# SCH_PCB_Project.net
KiCad netlist of a schematic drawn in EasyEDA
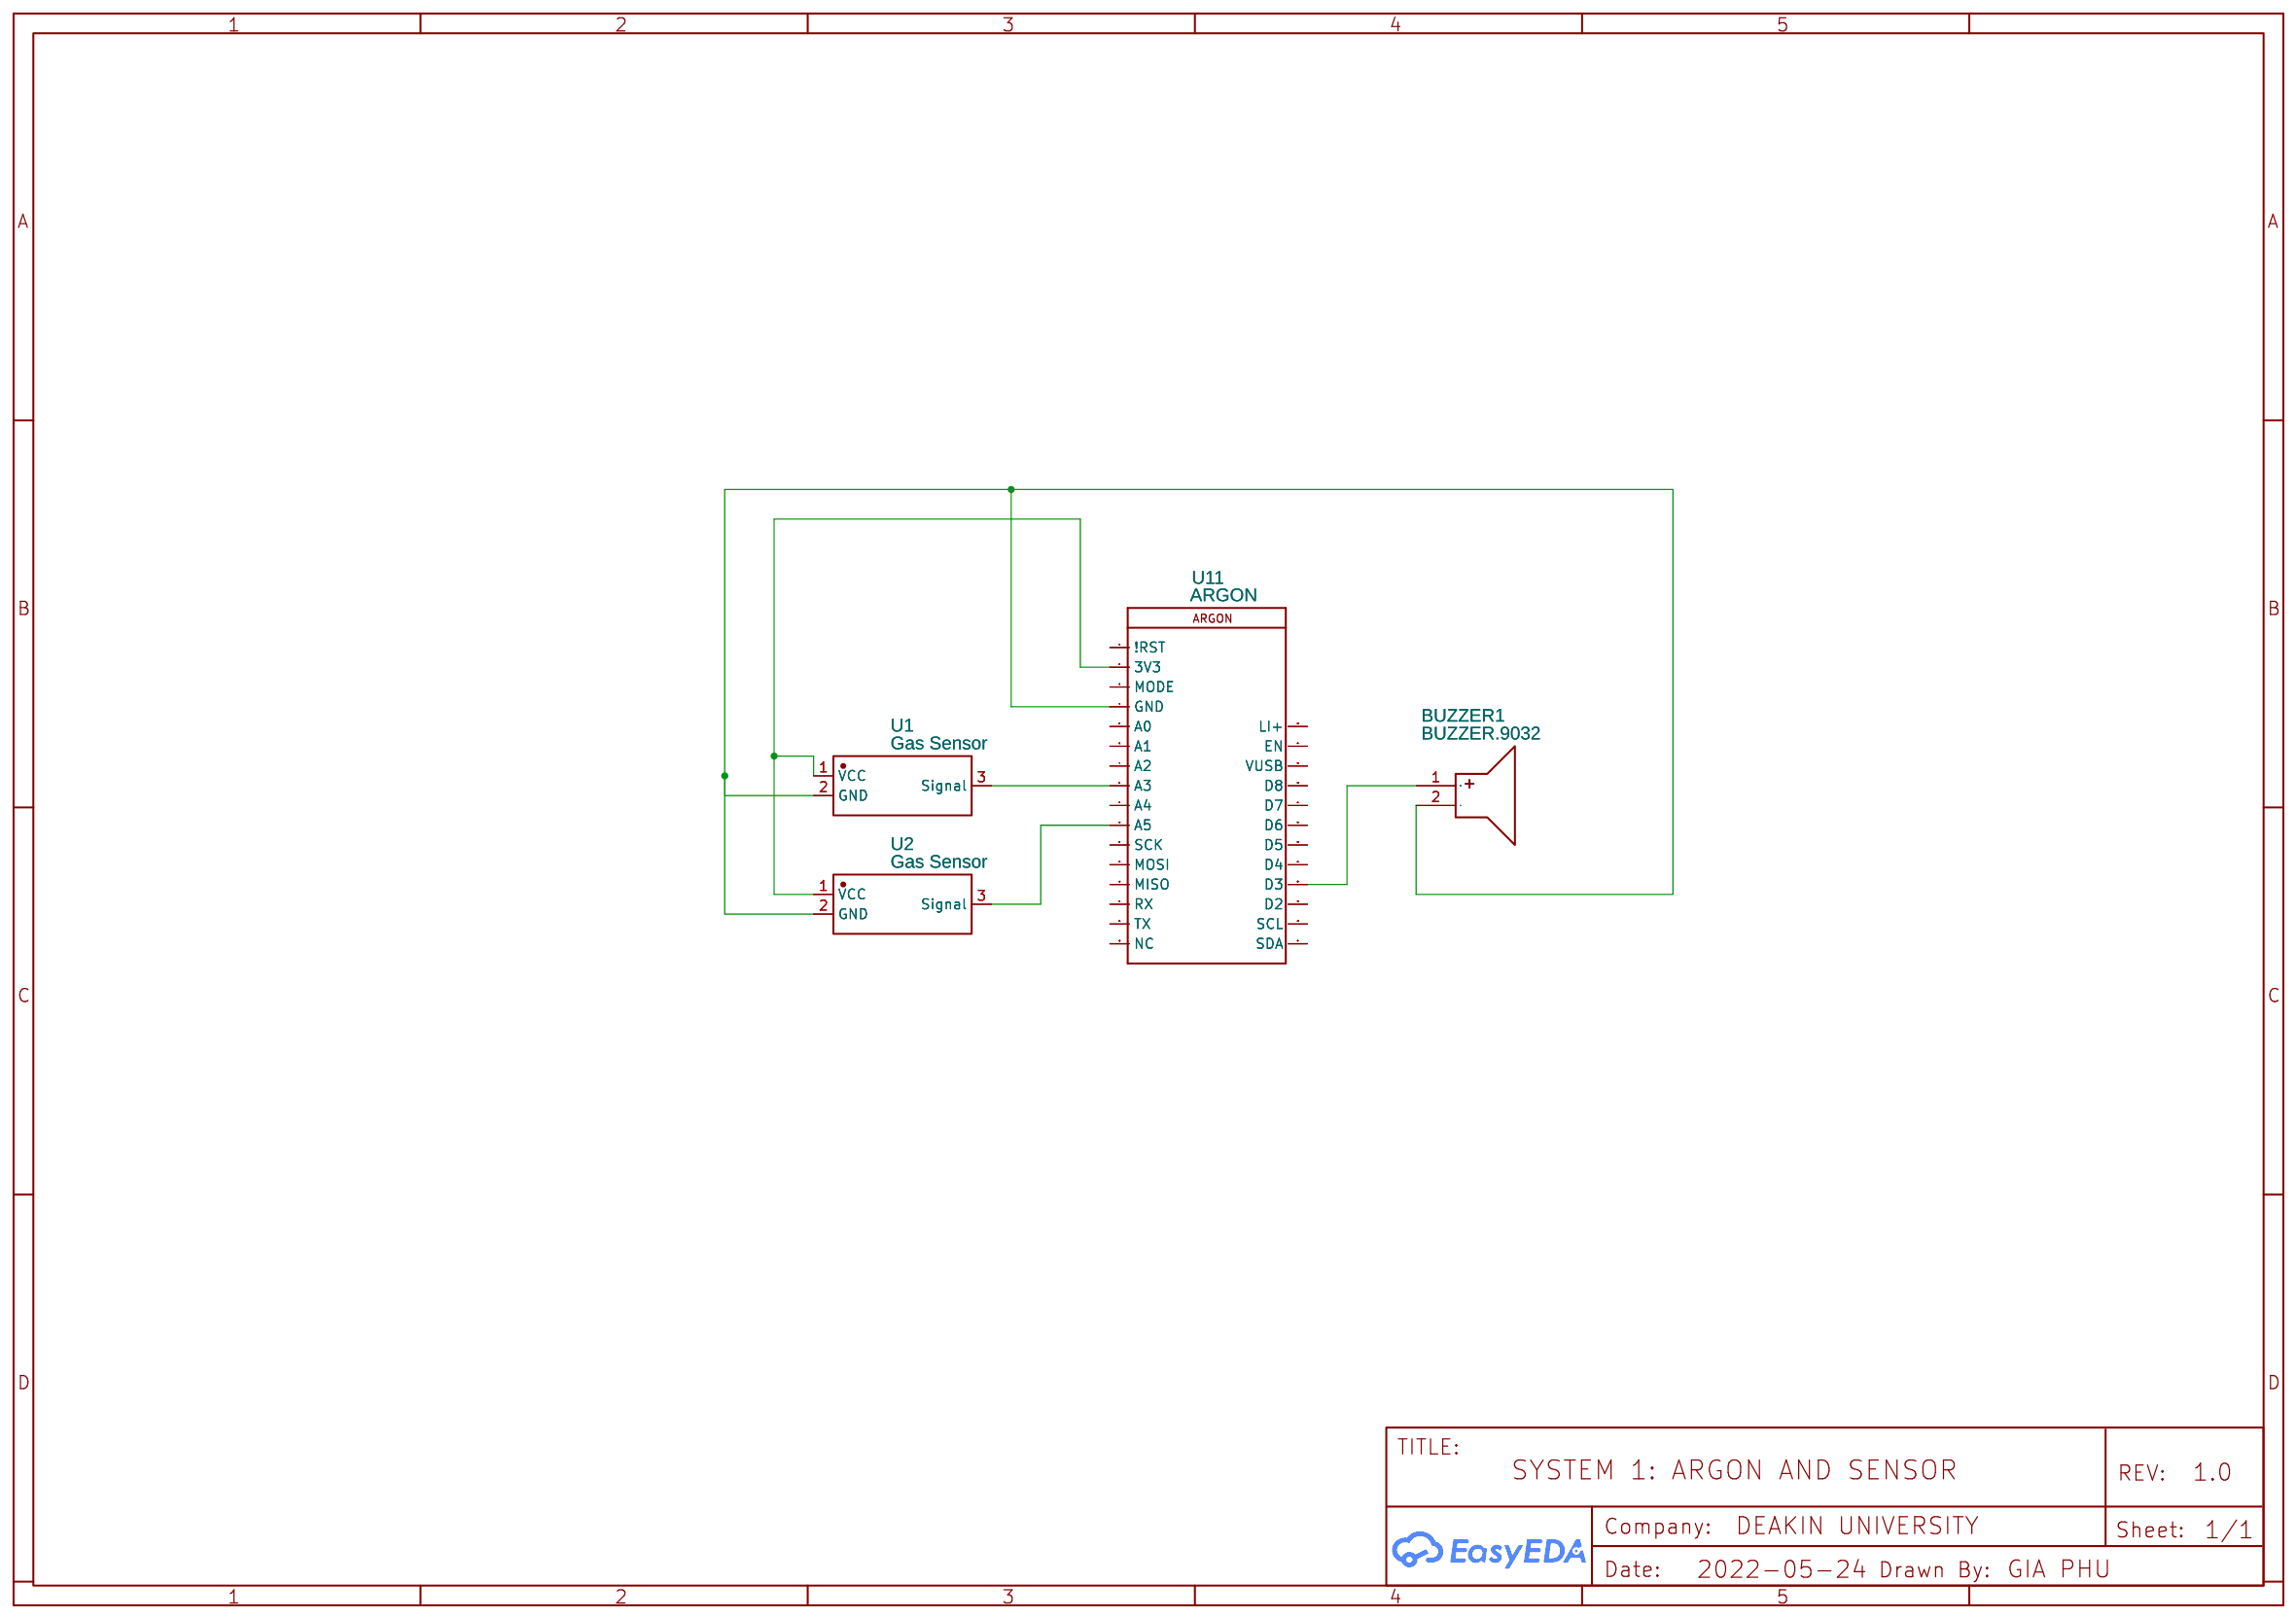
[diagram p0: Sheet_1]
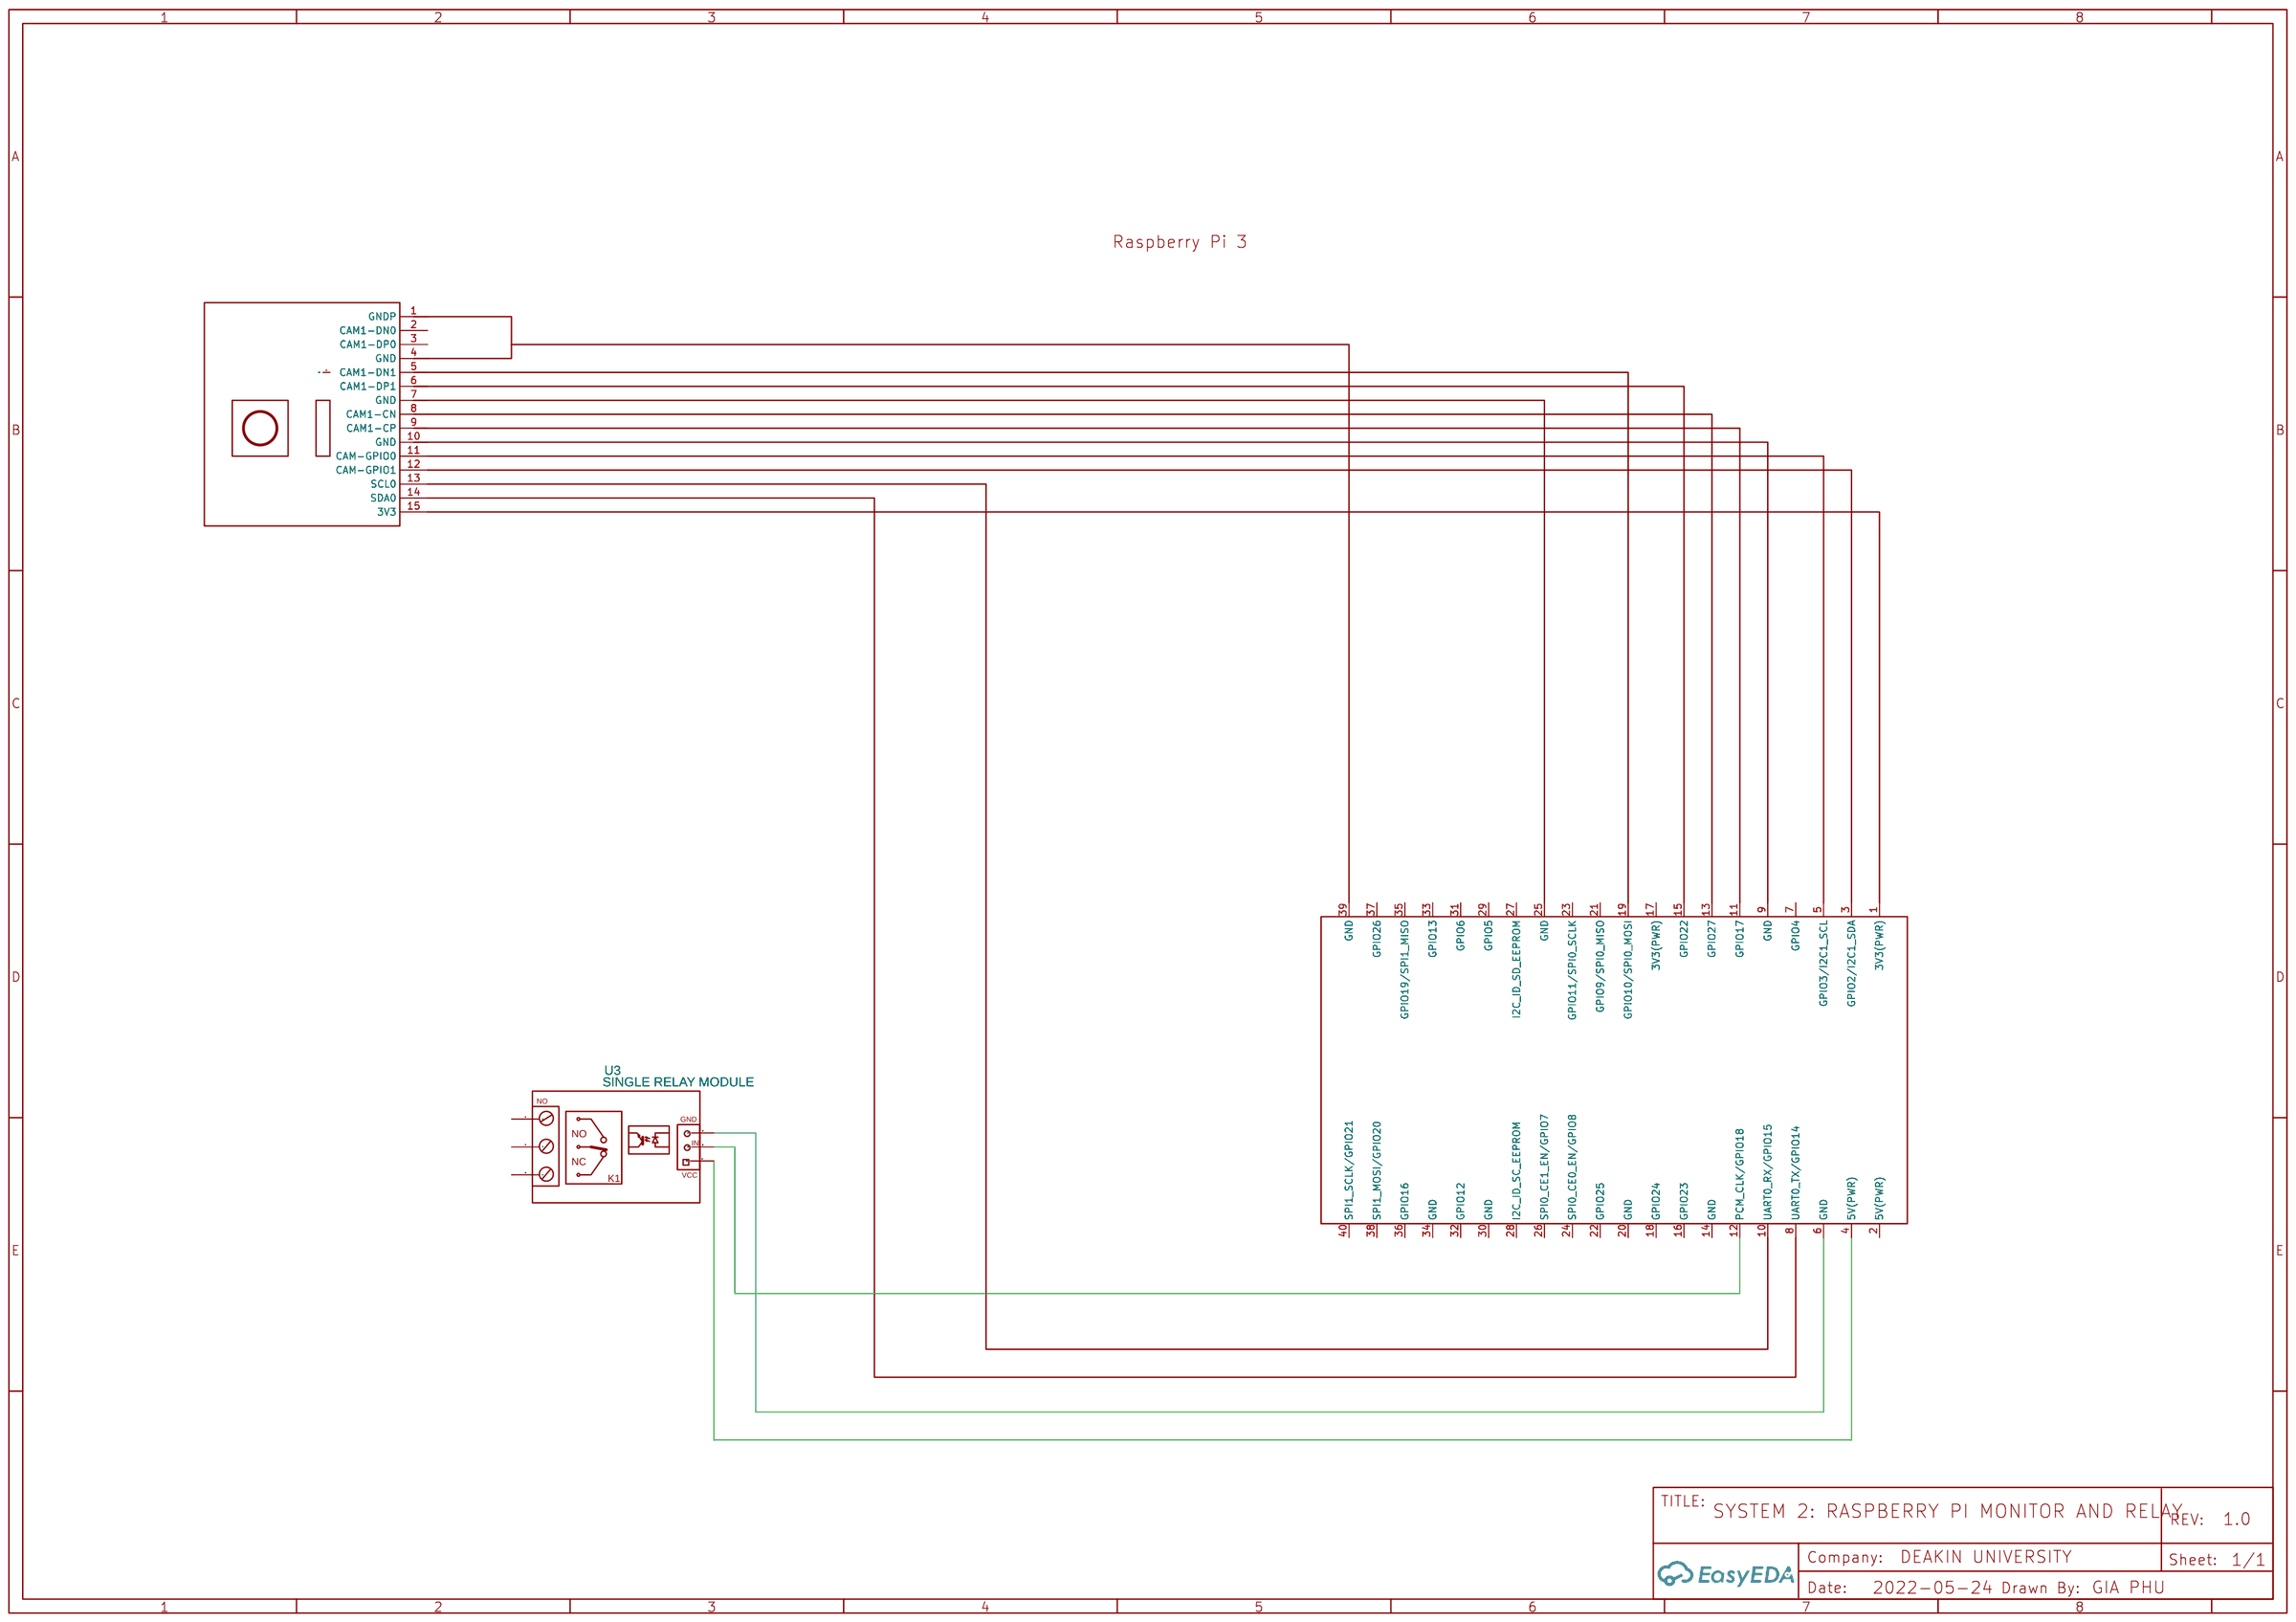
[diagram p1: Sheet_2]
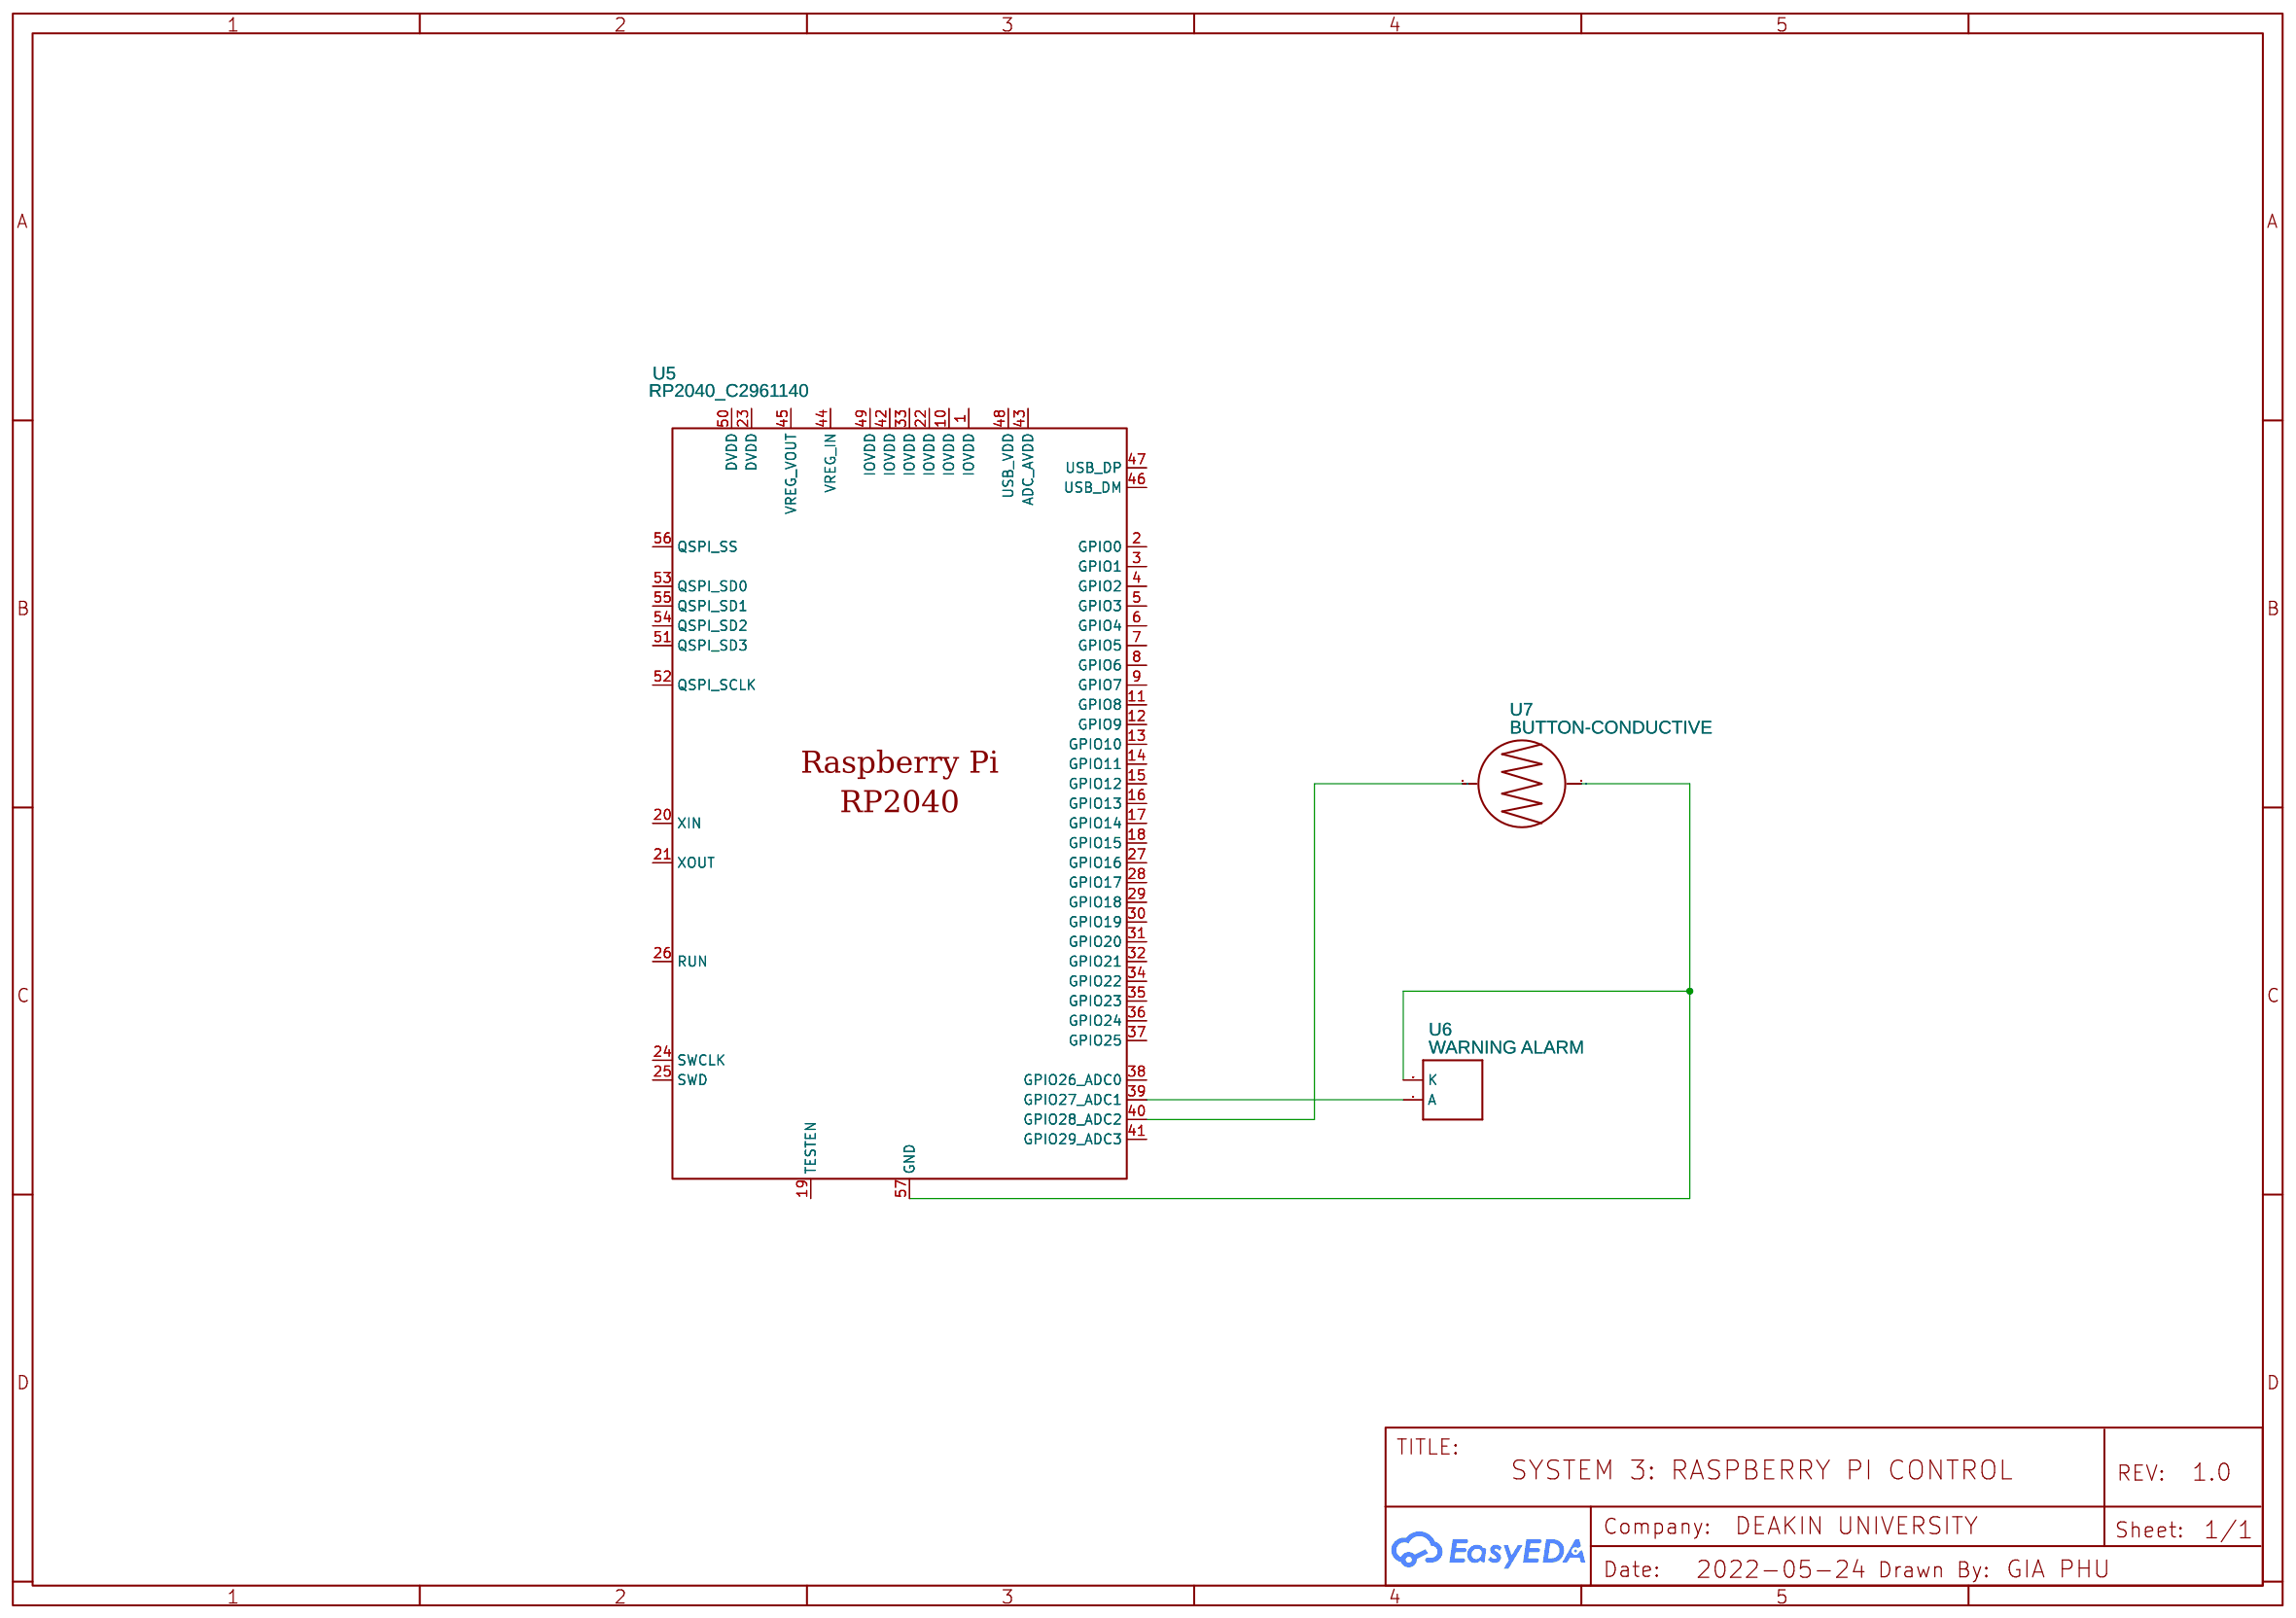
[diagram p2: Sheet_3]

(export (version "E")
  (design (tool "Eeschema 10.0.6"))
  (components
    (comp (ref "BUZZER1")
      (value "BUZZER.9032")
      (fields (field (name "BOM_Supplier Part") "C9900002564"))
      (libsource (lib "") (part "BUZZER.9032"))
    )
    (comp (ref "U1")
      (value "Gas Sensor")
      (fields
        (field (name "BOM_Manufacturer Part") "D210HM")
        (field (name "BOM_Supplier Part") "C9900004476")
      )
      (libsource (lib "") (part "D210HM"))
    )
    (comp (ref "U2")
      (value "Gas Sensor")
      (fields
        (field (name "BOM_Manufacturer Part") "D210HM")
        (field (name "BOM_Supplier Part") "C9900004476")
      )
      (libsource (lib "") (part "D210HM"))
    )
    (comp (ref "U11") (value "ARGON") (libsource (lib "") (part "ARGON")))
    (comp (ref "U3")
      (value "SINGLE RELAY MODULE")
      (fields
        (field (name "BOM_Manufacturer Part") "1-Channel 5V Relay Module w/ Opto-isolator")
        (field (name "BOM_Supplier Part") "SKU: 223429")
      )
      (libsource (lib "") (part "SINGLE RELAY MODULE"))
    )
    (comp (ref "U4")
      (value "raspberry pi3 and picamera_MIO")
      (libsource (lib "") (part "raspberry pi3 and picamera_MIO"))
    )
    (comp (ref "U5")
      (value "RP2040_C2961140")
      (fields (field (name "BOM_Manufacturer Part") "RP2040") (field (name "BOM_Supplier Part") "C2961140"))
      (libsource (lib "") (part "RP2040_C2961140"))
    )
    (comp (ref "U6") (value "WARNING ALARM") (libsource (lib "") (part "LCD_BACKLIGHT_PADS")))
    (comp (ref "U7") (value "BUTTON-CONDUCTIVE") (libsource (lib "") (part "BUTTON-CONDUCTIVE")))
  )
  (nets
    (net (code "1") (name "Net-(BUZZER1-+)") (class "Default")
      (node (ref "BUZZER1") (pin "1") (pinfunction "+_1") (pintype "unspecified"))
      (node (ref "U11") (pin "20") (pinfunction "D3_20") (pintype "bidirectional"))
    )
    (net (code "2") (name "Net-(BUZZER1--)") (class "Default")
      (node (ref "BUZZER1") (pin "2") (pinfunction "-_2") (pintype "unspecified"))
      (node (ref "U1") (pin "2") (pinfunction "GND_2") (pintype "unspecified"))
      (node (ref "U11") (pin "4") (pinfunction "GND_4") (pintype "bidirectional"))
      (node (ref "U2") (pin "2") (pinfunction "GND_2") (pintype "unspecified"))
    )
    (net (code "3") (name "Net-(U1-Signal)") (class "Default")
      (node (ref "U1") (pin "3") (pinfunction "Signal_3") (pintype "unspecified"))
      (node (ref "U11") (pin "8") (pinfunction "A3_8") (pintype "bidirectional"))
    )
    (net (code "4") (name "Net-(U1-VCC)") (class "Default")
      (node (ref "U1") (pin "1") (pinfunction "VCC_1") (pintype "unspecified"))
      (node (ref "U11") (pin "2") (pinfunction "3V3_2") (pintype "bidirectional"))
      (node (ref "U2") (pin "1") (pinfunction "VCC_1") (pintype "unspecified"))
    )
    (net (code "5") (name "Net-(U3-Pad13)") (class "Default")
      (node (ref "U3") (pin "13") (pinfunction "13_13") (pintype "input"))
      (node (ref "U4") (pin "4") (pinfunction "5V(PWR)_4") (pintype "passive"))
    )
    (net (code "6") (name "Net-(U3-Pad14)") (class "Default")
      (node (ref "U3") (pin "14") (pinfunction "14_14") (pintype "input"))
      (node (ref "U4") (pin "6") (pinfunction "GND_6") (pintype "passive"))
    )
    (net (code "7") (name "Net-(U4-PCM_CLK{slash}GPIO18)") (class "Default")
      (node (ref "U3") (pin "15") (pinfunction "15_15") (pintype "input"))
      (node (ref "U4") (pin "12") (pinfunction "PCM_CLK/GPIO18_12") (pintype "bidirectional"))
    )
    (net (code "8") (name "Net-(U5-GND)") (class "Default")
      (node (ref "U5") (pin "57") (pinfunction "GND_57") (pintype "bidirectional"))
      (node (ref "U6") (pin "P$2") (pinfunction "K_P$2") (pintype "unspecified"))
      (node (ref "U7") (pin "2") (pinfunction "2_2") (pintype "unspecified"))
    )
    (net (code "9") (name "Net-(U5-GPIO27_ADC1)") (class "Default")
      (node (ref "U5") (pin "39") (pinfunction "GPIO27_ADC1_39") (pintype "bidirectional"))
      (node (ref "U6") (pin "P$1") (pinfunction "A_P$1") (pintype "unspecified"))
    )
    (net (code "10") (name "Net-(U5-GPIO28_ADC2)") (class "Default")
      (node (ref "U5") (pin "40") (pinfunction "GPIO28_ADC2_40") (pintype "bidirectional"))
      (node (ref "U7") (pin "1") (pinfunction "1_1") (pintype "unspecified"))
    )
    (net (code "11") (name "Net-(U11-A5)") (class "Default")
      (node (ref "U11") (pin "10") (pinfunction "A5_10") (pintype "bidirectional"))
      (node (ref "U2") (pin "3") (pinfunction "Signal_3") (pintype "unspecified"))
    )
    (net (code "12") (name "unconnected-(U3-Pad1)") (class "Default")
      (node (ref "U3") (pin "1") (pinfunction "1_1") (pintype "unspecified"))
    )
    (net (code "13") (name "unconnected-(U3-Pad2)") (class "Default")
      (node (ref "U3") (pin "2") (pinfunction "2_2") (pintype "unspecified"))
    )
    (net (code "14") (name "unconnected-(U3-Pad3)") (class "Default")
      (node (ref "U3") (pin "3") (pinfunction "3_3") (pintype "unspecified"))
    )
    (net (code "15") (name "unconnected-(U4-3V3(PWR)-Pad1)") (class "Default")
      (node (ref "U4") (pin "1") (pinfunction "3V3(PWR)_1") (pintype "passive"))
    )
    (net (code "16") (name "unconnected-(U4-3V3(PWR)-Pad17)") (class "Default")
      (node (ref "U4") (pin "17") (pinfunction "3V3(PWR)_17") (pintype "passive"))
    )
    (net (code "17") (name "unconnected-(U4-3V3-Pad15)") (class "Default")
      (node (ref "U4") (pin "15") (pinfunction "3V3_15") (pintype "unspecified"))
    )
    (net (code "18") (name "unconnected-(U4-5V(PWR)-Pad2)") (class "Default")
      (node (ref "U4") (pin "2") (pinfunction "5V(PWR)_2") (pintype "passive"))
    )
    (net (code "19") (name "unconnected-(U4-CAM-GPIO0-Pad11)") (class "Default")
      (node (ref "U4") (pin "11") (pinfunction "CAM-GPIO0_11") (pintype "unspecified"))
    )
    (net (code "20") (name "unconnected-(U4-CAM-GPIO1-Pad12)") (class "Default")
      (node (ref "U4") (pin "12") (pinfunction "CAM-GPIO1_12") (pintype "unspecified"))
    )
    (net (code "21") (name "unconnected-(U4-CAM1-CN-Pad8)") (class "Default")
      (node (ref "U4") (pin "8") (pinfunction "CAM1-CN_8") (pintype "unspecified"))
    )
    (net (code "22") (name "unconnected-(U4-CAM1-CP-Pad9)") (class "Default")
      (node (ref "U4") (pin "9") (pinfunction "CAM1-CP_9") (pintype "unspecified"))
    )
    (net (code "23") (name "unconnected-(U4-CAM1-DN0-Pad2)") (class "Default")
      (node (ref "U4") (pin "2") (pinfunction "CAM1-DN0_2") (pintype "unspecified"))
    )
    (net (code "24") (name "unconnected-(U4-CAM1-DN1-Pad5)") (class "Default")
      (node (ref "U4") (pin "5") (pinfunction "CAM1-DN1_5") (pintype "unspecified"))
    )
    (net (code "25") (name "unconnected-(U4-CAM1-DP0-Pad3)") (class "Default")
      (node (ref "U4") (pin "3") (pinfunction "CAM1-DP0_3") (pintype "unspecified"))
    )
    (net (code "26") (name "unconnected-(U4-CAM1-DP1-Pad6)") (class "Default")
      (node (ref "U4") (pin "6") (pinfunction "CAM1-DP1_6") (pintype "unspecified"))
    )
    (net (code "27") (name "unconnected-(U4-CSI_Port-Pad1)") (class "Default")
      (node (ref "U4") (pin "1") (pinfunction "CSI_Port_1") (pintype "unspecified"))
    )
    (net (code "28") (name "unconnected-(U4-GND-Pad4)") (class "Default")
      (node (ref "U4") (pin "4") (pinfunction "GND_4") (pintype "unspecified"))
    )
    (net (code "29") (name "unconnected-(U4-GND-Pad7)") (class "Default")
      (node (ref "U4") (pin "7") (pinfunction "GND_7") (pintype "unspecified"))
    )
    (net (code "30") (name "unconnected-(U4-GND-Pad9)") (class "Default")
      (node (ref "U4") (pin "9") (pinfunction "GND_9") (pintype "passive"))
    )
    (net (code "31") (name "unconnected-(U4-GND-Pad10)") (class "Default")
      (node (ref "U4") (pin "10") (pinfunction "GND_10") (pintype "unspecified"))
    )
    (net (code "32") (name "unconnected-(U4-GND-Pad14)") (class "Default")
      (node (ref "U4") (pin "14") (pinfunction "GND_14") (pintype "passive"))
    )
    (net (code "33") (name "unconnected-(U4-GND-Pad20)") (class "Default")
      (node (ref "U4") (pin "20") (pinfunction "GND_20") (pintype "passive"))
    )
    (net (code "34") (name "unconnected-(U4-GND-Pad25)") (class "Default")
      (node (ref "U4") (pin "25") (pinfunction "GND_25") (pintype "passive"))
    )
    (net (code "35") (name "unconnected-(U4-GND-Pad30)") (class "Default")
      (node (ref "U4") (pin "30") (pinfunction "GND_30") (pintype "passive"))
    )
    (net (code "36") (name "unconnected-(U4-GND-Pad34)") (class "Default")
      (node (ref "U4") (pin "34") (pinfunction "GND_34") (pintype "passive"))
    )
    (net (code "37") (name "unconnected-(U4-GND-Pad39)") (class "Default")
      (node (ref "U4") (pin "39") (pinfunction "GND_39") (pintype "passive"))
    )
    (net (code "38") (name "unconnected-(U4-GNDP-Pad1)") (class "Default")
      (node (ref "U4") (pin "1") (pinfunction "GNDP_1") (pintype "unspecified"))
    )
    (net (code "39") (name "unconnected-(U4-GPIO2{slash}I2C1_SDA-Pad3)") (class "Default")
      (node (ref "U4") (pin "3") (pinfunction "GPIO2/I2C1_SDA_3") (pintype "bidirectional"))
    )
    (net (code "40") (name "unconnected-(U4-GPIO3{slash}I2C1_SCL-Pad5)") (class "Default")
      (node (ref "U4") (pin "5") (pinfunction "GPIO3/I2C1_SCL_5") (pintype "bidirectional"))
    )
    (net (code "41") (name "unconnected-(U4-GPIO4-Pad7)") (class "Default")
      (node (ref "U4") (pin "7") (pinfunction "GPIO4_7") (pintype "bidirectional"))
    )
    (net (code "42") (name "unconnected-(U4-GPIO5-Pad29)") (class "Default")
      (node (ref "U4") (pin "29") (pinfunction "GPIO5_29") (pintype "bidirectional"))
    )
    (net (code "43") (name "unconnected-(U4-GPIO6-Pad31)") (class "Default")
      (node (ref "U4") (pin "31") (pinfunction "GPIO6_31") (pintype "bidirectional"))
    )
    (net (code "44") (name "unconnected-(U4-GPIO9{slash}SPI0_MISO-Pad21)") (class "Default")
      (node (ref "U4") (pin "21") (pinfunction "GPIO9/SPI0_MISO_21") (pintype "bidirectional"))
    )
    (net (code "45") (name "unconnected-(U4-GPIO10{slash}SPI0_MOSI-Pad19)") (class "Default")
      (node (ref "U4") (pin "19") (pinfunction "GPIO10/SPI0_MOSI_19") (pintype "bidirectional"))
    )
    (net (code "46") (name "unconnected-(U4-GPIO11{slash}SPI0_SCLK-Pad23)") (class "Default")
      (node (ref "U4") (pin "23") (pinfunction "GPIO11/SPI0_SCLK_23") (pintype "bidirectional"))
    )
    (net (code "47") (name "unconnected-(U4-GPIO12-Pad32)") (class "Default")
      (node (ref "U4") (pin "32") (pinfunction "GPIO12_32") (pintype "bidirectional"))
    )
    (net (code "48") (name "unconnected-(U4-GPIO13-Pad33)") (class "Default")
      (node (ref "U4") (pin "33") (pinfunction "GPIO13_33") (pintype "bidirectional"))
    )
    (net (code "49") (name "unconnected-(U4-GPIO16-Pad36)") (class "Default")
      (node (ref "U4") (pin "36") (pinfunction "GPIO16_36") (pintype "bidirectional"))
    )
    (net (code "50") (name "unconnected-(U4-GPIO17-Pad11)") (class "Default")
      (node (ref "U4") (pin "11") (pinfunction "GPIO17_11") (pintype "bidirectional"))
    )
    (net (code "51") (name "unconnected-(U4-GPIO19{slash}SPI1_MISO-Pad35)") (class "Default")
      (node (ref "U4") (pin "35") (pinfunction "GPIO19/SPI1_MISO_35") (pintype "bidirectional"))
    )
    (net (code "52") (name "unconnected-(U4-GPIO22-Pad15)") (class "Default")
      (node (ref "U4") (pin "15") (pinfunction "GPIO22_15") (pintype "output"))
    )
    (net (code "53") (name "unconnected-(U4-GPIO23-Pad16)") (class "Default")
      (node (ref "U4") (pin "16") (pinfunction "GPIO23_16") (pintype "bidirectional"))
    )
    (net (code "54") (name "unconnected-(U4-GPIO24-Pad18)") (class "Default")
      (node (ref "U4") (pin "18") (pinfunction "GPIO24_18") (pintype "bidirectional"))
    )
    (net (code "55") (name "unconnected-(U4-GPIO25-Pad22)") (class "Default")
      (node (ref "U4") (pin "22") (pinfunction "GPIO25_22") (pintype "bidirectional"))
    )
    (net (code "56") (name "unconnected-(U4-GPIO26-Pad37)") (class "Default")
      (node (ref "U4") (pin "37") (pinfunction "GPIO26_37") (pintype "bidirectional"))
    )
    (net (code "57") (name "unconnected-(U4-GPIO27-Pad13)") (class "Default")
      (node (ref "U4") (pin "13") (pinfunction "GPIO27_13") (pintype "bidirectional"))
    )
    (net (code "58") (name "unconnected-(U4-I2C_ID_SC_EEPROM-Pad28)") (class "Default")
      (node (ref "U4") (pin "28") (pinfunction "I2C_ID_SC_EEPROM_28") (pintype "unspecified"))
    )
    (net (code "59") (name "unconnected-(U4-I2C_ID_SD_EEPROM-Pad27)") (class "Default")
      (node (ref "U4") (pin "27") (pinfunction "I2C_ID_SD_EEPROM_27") (pintype "unspecified"))
    )
    (net (code "60") (name "unconnected-(U4-SCL0-Pad13)") (class "Default")
      (node (ref "U4") (pin "13") (pinfunction "SCL0_13") (pintype "unspecified"))
    )
    (net (code "61") (name "unconnected-(U4-SDA0-Pad14)") (class "Default")
      (node (ref "U4") (pin "14") (pinfunction "SDA0_14") (pintype "unspecified"))
    )
    (net (code "62") (name "unconnected-(U4-SPI0_CE0_EN{slash}GPIO8-Pad24)") (class "Default")
      (node (ref "U4") (pin "24") (pinfunction "SPI0_CE0_EN/GPIO8_24") (pintype "bidirectional"))
    )
    (net (code "63") (name "unconnected-(U4-SPI0_CE1_EN{slash}GPIO7-Pad26)") (class "Default")
      (node (ref "U4") (pin "26") (pinfunction "SPI0_CE1_EN/GPIO7_26") (pintype "bidirectional"))
    )
    (net (code "64") (name "unconnected-(U4-SPI1_MOSI{slash}GPIO20-Pad38)") (class "Default")
      (node (ref "U4") (pin "38") (pinfunction "SPI1_MOSI/GPIO20_38") (pintype "bidirectional"))
    )
    (net (code "65") (name "unconnected-(U4-SPI1_SCLK{slash}GPIO21-Pad40)") (class "Default")
      (node (ref "U4") (pin "40") (pinfunction "SPI1_SCLK/GPIO21_40") (pintype "bidirectional"))
    )
    (net (code "66") (name "unconnected-(U4-UART0_RX{slash}GPIO15-Pad10)") (class "Default")
      (node (ref "U4") (pin "10") (pinfunction "UART0_RX/GPIO15_10") (pintype "bidirectional"))
    )
    (net (code "67") (name "unconnected-(U4-UART0_TX{slash}GPIO14-Pad8)") (class "Default")
      (node (ref "U4") (pin "8") (pinfunction "UART0_TX/GPIO14_8") (pintype "passive"))
    )
    (net (code "68") (name "unconnected-(U5-ADC_AVDD-Pad43)") (class "Default")
      (node (ref "U5") (pin "43") (pinfunction "ADC_AVDD_43") (pintype "bidirectional"))
    )
    (net (code "69") (name "unconnected-(U5-DVDD-Pad23)") (class "Default")
      (node (ref "U5") (pin "23") (pinfunction "DVDD_23") (pintype "bidirectional"))
    )
    (net (code "70") (name "unconnected-(U5-DVDD-Pad50)") (class "Default")
      (node (ref "U5") (pin "50") (pinfunction "DVDD_50") (pintype "bidirectional"))
    )
    (net (code "71") (name "unconnected-(U5-GPIO0-Pad2)") (class "Default")
      (node (ref "U5") (pin "2") (pinfunction "GPIO0_2") (pintype "bidirectional"))
    )
    (net (code "72") (name "unconnected-(U5-GPIO1-Pad3)") (class "Default")
      (node (ref "U5") (pin "3") (pinfunction "GPIO1_3") (pintype "bidirectional"))
    )
    (net (code "73") (name "unconnected-(U5-GPIO2-Pad4)") (class "Default")
      (node (ref "U5") (pin "4") (pinfunction "GPIO2_4") (pintype "bidirectional"))
    )
    (net (code "74") (name "unconnected-(U5-GPIO3-Pad5)") (class "Default")
      (node (ref "U5") (pin "5") (pinfunction "GPIO3_5") (pintype "bidirectional"))
    )
    (net (code "75") (name "unconnected-(U5-GPIO4-Pad6)") (class "Default")
      (node (ref "U5") (pin "6") (pinfunction "GPIO4_6") (pintype "bidirectional"))
    )
    (net (code "76") (name "unconnected-(U5-GPIO5-Pad7)") (class "Default")
      (node (ref "U5") (pin "7") (pinfunction "GPIO5_7") (pintype "bidirectional"))
    )
    (net (code "77") (name "unconnected-(U5-GPIO6-Pad8)") (class "Default")
      (node (ref "U5") (pin "8") (pinfunction "GPIO6_8") (pintype "bidirectional"))
    )
    (net (code "78") (name "unconnected-(U5-GPIO7-Pad9)") (class "Default")
      (node (ref "U5") (pin "9") (pinfunction "GPIO7_9") (pintype "bidirectional"))
    )
    (net (code "79") (name "unconnected-(U5-GPIO8-Pad11)") (class "Default")
      (node (ref "U5") (pin "11") (pinfunction "GPIO8_11") (pintype "bidirectional"))
    )
    (net (code "80") (name "unconnected-(U5-GPIO9-Pad12)") (class "Default")
      (node (ref "U5") (pin "12") (pinfunction "GPIO9_12") (pintype "bidirectional"))
    )
    (net (code "81") (name "unconnected-(U5-GPIO10-Pad13)") (class "Default")
      (node (ref "U5") (pin "13") (pinfunction "GPIO10_13") (pintype "bidirectional"))
    )
    (net (code "82") (name "unconnected-(U5-GPIO11-Pad14)") (class "Default")
      (node (ref "U5") (pin "14") (pinfunction "GPIO11_14") (pintype "bidirectional"))
    )
    (net (code "83") (name "unconnected-(U5-GPIO12-Pad15)") (class "Default")
      (node (ref "U5") (pin "15") (pinfunction "GPIO12_15") (pintype "bidirectional"))
    )
    (net (code "84") (name "unconnected-(U5-GPIO13-Pad16)") (class "Default")
      (node (ref "U5") (pin "16") (pinfunction "GPIO13_16") (pintype "bidirectional"))
    )
    (net (code "85") (name "unconnected-(U5-GPIO14-Pad17)") (class "Default")
      (node (ref "U5") (pin "17") (pinfunction "GPIO14_17") (pintype "bidirectional"))
    )
    (net (code "86") (name "unconnected-(U5-GPIO15-Pad18)") (class "Default")
      (node (ref "U5") (pin "18") (pinfunction "GPIO15_18") (pintype "bidirectional"))
    )
    (net (code "87") (name "unconnected-(U5-GPIO16-Pad27)") (class "Default")
      (node (ref "U5") (pin "27") (pinfunction "GPIO16_27") (pintype "bidirectional"))
    )
    (net (code "88") (name "unconnected-(U5-GPIO17-Pad28)") (class "Default")
      (node (ref "U5") (pin "28") (pinfunction "GPIO17_28") (pintype "bidirectional"))
    )
    (net (code "89") (name "unconnected-(U5-GPIO18-Pad29)") (class "Default")
      (node (ref "U5") (pin "29") (pinfunction "GPIO18_29") (pintype "bidirectional"))
    )
    (net (code "90") (name "unconnected-(U5-GPIO19-Pad30)") (class "Default")
      (node (ref "U5") (pin "30") (pinfunction "GPIO19_30") (pintype "bidirectional"))
    )
    (net (code "91") (name "unconnected-(U5-GPIO20-Pad31)") (class "Default")
      (node (ref "U5") (pin "31") (pinfunction "GPIO20_31") (pintype "bidirectional"))
    )
    (net (code "92") (name "unconnected-(U5-GPIO21-Pad32)") (class "Default")
      (node (ref "U5") (pin "32") (pinfunction "GPIO21_32") (pintype "bidirectional"))
    )
    (net (code "93") (name "unconnected-(U5-GPIO22-Pad34)") (class "Default")
      (node (ref "U5") (pin "34") (pinfunction "GPIO22_34") (pintype "bidirectional"))
    )
    (net (code "94") (name "unconnected-(U5-GPIO23-Pad35)") (class "Default")
      (node (ref "U5") (pin "35") (pinfunction "GPIO23_35") (pintype "bidirectional"))
    )
    (net (code "95") (name "unconnected-(U5-GPIO24-Pad36)") (class "Default")
      (node (ref "U5") (pin "36") (pinfunction "GPIO24_36") (pintype "bidirectional"))
    )
    (net (code "96") (name "unconnected-(U5-GPIO25-Pad37)") (class "Default")
      (node (ref "U5") (pin "37") (pinfunction "GPIO25_37") (pintype "bidirectional"))
    )
    (net (code "97") (name "unconnected-(U5-GPIO26_ADC0-Pad38)") (class "Default")
      (node (ref "U5") (pin "38") (pinfunction "GPIO26_ADC0_38") (pintype "bidirectional"))
    )
    (net (code "98") (name "unconnected-(U5-GPIO29_ADC3-Pad41)") (class "Default")
      (node (ref "U5") (pin "41") (pinfunction "GPIO29_ADC3_41") (pintype "bidirectional"))
    )
    (net (code "99") (name "unconnected-(U5-IOVDD-Pad1)") (class "Default")
      (node (ref "U5") (pin "1") (pinfunction "IOVDD_1") (pintype "bidirectional"))
    )
    (net (code "100") (name "unconnected-(U5-IOVDD-Pad10)") (class "Default")
      (node (ref "U5") (pin "10") (pinfunction "IOVDD_10") (pintype "bidirectional"))
    )
    (net (code "101") (name "unconnected-(U5-IOVDD-Pad22)") (class "Default")
      (node (ref "U5") (pin "22") (pinfunction "IOVDD_22") (pintype "bidirectional"))
    )
    (net (code "102") (name "unconnected-(U5-IOVDD-Pad33)") (class "Default")
      (node (ref "U5") (pin "33") (pinfunction "IOVDD_33") (pintype "bidirectional"))
    )
    (net (code "103") (name "unconnected-(U5-IOVDD-Pad42)") (class "Default")
      (node (ref "U5") (pin "42") (pinfunction "IOVDD_42") (pintype "bidirectional"))
    )
    (net (code "104") (name "unconnected-(U5-IOVDD-Pad49)") (class "Default")
      (node (ref "U5") (pin "49") (pinfunction "IOVDD_49") (pintype "bidirectional"))
    )
    (net (code "105") (name "unconnected-(U5-QSPI_SCLK-Pad52)") (class "Default")
      (node (ref "U5") (pin "52") (pinfunction "QSPI_SCLK_52") (pintype "output"))
    )
    (net (code "106") (name "unconnected-(U5-QSPI_SD0-Pad53)") (class "Default")
      (node (ref "U5") (pin "53") (pinfunction "QSPI_SD0_53") (pintype "bidirectional"))
    )
    (net (code "107") (name "unconnected-(U5-QSPI_SD1-Pad55)") (class "Default")
      (node (ref "U5") (pin "55") (pinfunction "QSPI_SD1_55") (pintype "bidirectional"))
    )
    (net (code "108") (name "unconnected-(U5-QSPI_SD2-Pad54)") (class "Default")
      (node (ref "U5") (pin "54") (pinfunction "QSPI_SD2_54") (pintype "bidirectional"))
    )
    (net (code "109") (name "unconnected-(U5-QSPI_SD3-Pad51)") (class "Default")
      (node (ref "U5") (pin "51") (pinfunction "QSPI_SD3_51") (pintype "bidirectional"))
    )
    (net (code "110") (name "unconnected-(U5-QSPI_SS-Pad56)") (class "Default")
      (node (ref "U5") (pin "56") (pinfunction "QSPI_SS_56") (pintype "bidirectional"))
    )
    (net (code "111") (name "unconnected-(U5-RUN-Pad26)") (class "Default")
      (node (ref "U5") (pin "26") (pinfunction "RUN_26") (pintype "input"))
    )
    (net (code "112") (name "unconnected-(U5-SWCLK-Pad24)") (class "Default")
      (node (ref "U5") (pin "24") (pinfunction "SWCLK_24") (pintype "output"))
    )
    (net (code "113") (name "unconnected-(U5-SWD-Pad25)") (class "Default")
      (node (ref "U5") (pin "25") (pinfunction "SWD_25") (pintype "bidirectional"))
    )
    (net (code "114") (name "unconnected-(U5-TESTEN-Pad19)") (class "Default")
      (node (ref "U5") (pin "19") (pinfunction "TESTEN_19") (pintype "unspecified"))
    )
    (net (code "115") (name "unconnected-(U5-USB_DM-Pad46)") (class "Default")
      (node (ref "U5") (pin "46") (pinfunction "USB_DM_46") (pintype "bidirectional"))
    )
    (net (code "116") (name "unconnected-(U5-USB_DP-Pad47)") (class "Default")
      (node (ref "U5") (pin "47") (pinfunction "USB_DP_47") (pintype "bidirectional"))
    )
    (net (code "117") (name "unconnected-(U5-USB_VDD-Pad48)") (class "Default")
      (node (ref "U5") (pin "48") (pinfunction "USB_VDD_48") (pintype "bidirectional"))
    )
    (net (code "118") (name "unconnected-(U5-VREG_IN-Pad44)") (class "Default")
      (node (ref "U5") (pin "44") (pinfunction "VREG_IN_44") (pintype "bidirectional"))
    )
    (net (code "119") (name "unconnected-(U5-VREG_VOUT-Pad45)") (class "Default")
      (node (ref "U5") (pin "45") (pinfunction "VREG_VOUT_45") (pintype "bidirectional"))
    )
    (net (code "120") (name "unconnected-(U5-XIN-Pad20)") (class "Default")
      (node (ref "U5") (pin "20") (pinfunction "XIN_20") (pintype "input"))
    )
    (net (code "121") (name "unconnected-(U5-XOUT-Pad21)") (class "Default")
      (node (ref "U5") (pin "21") (pinfunction "XOUT_21") (pintype "unspecified"))
    )
    (net (code "122") (name "unconnected-(U11-!RST-Pad1)") (class "Default")
      (node (ref "U11") (pin "1") (pinfunction "!RST_1") (pintype "bidirectional"))
    )
    (net (code "123") (name "unconnected-(U11-A0-Pad5)") (class "Default")
      (node (ref "U11") (pin "5") (pinfunction "A0_5") (pintype "bidirectional"))
    )
    (net (code "124") (name "unconnected-(U11-A1-Pad6)") (class "Default")
      (node (ref "U11") (pin "6") (pinfunction "A1_6") (pintype "bidirectional"))
    )
    (net (code "125") (name "unconnected-(U11-A2-Pad7)") (class "Default")
      (node (ref "U11") (pin "7") (pinfunction "A2_7") (pintype "bidirectional"))
    )
    (net (code "126") (name "unconnected-(U11-A4-Pad9)") (class "Default")
      (node (ref "U11") (pin "9") (pinfunction "A4_9") (pintype "bidirectional"))
    )
    (net (code "127") (name "unconnected-(U11-D2-Pad19)") (class "Default")
      (node (ref "U11") (pin "19") (pinfunction "D2_19") (pintype "bidirectional"))
    )
    (net (code "128") (name "unconnected-(U11-D4-Pad21)") (class "Default")
      (node (ref "U11") (pin "21") (pinfunction "D4_21") (pintype "bidirectional"))
    )
    (net (code "129") (name "unconnected-(U11-D5-Pad22)") (class "Default")
      (node (ref "U11") (pin "22") (pinfunction "D5_22") (pintype "bidirectional"))
    )
    (net (code "130") (name "unconnected-(U11-D6-Pad23)") (class "Default")
      (node (ref "U11") (pin "23") (pinfunction "D6_23") (pintype "bidirectional"))
    )
    (net (code "131") (name "unconnected-(U11-D7-Pad24)") (class "Default")
      (node (ref "U11") (pin "24") (pinfunction "D7_24") (pintype "bidirectional"))
    )
    (net (code "132") (name "unconnected-(U11-D8-Pad25)") (class "Default")
      (node (ref "U11") (pin "25") (pinfunction "D8_25") (pintype "bidirectional"))
    )
    (net (code "133") (name "unconnected-(U11-EN-Pad27)") (class "Default")
      (node (ref "U11") (pin "27") (pinfunction "EN_27") (pintype "bidirectional"))
    )
    (net (code "134") (name "unconnected-(U11-LI+-Pad28)") (class "Default")
      (node (ref "U11") (pin "28") (pinfunction "LI+_28") (pintype "bidirectional"))
    )
    (net (code "135") (name "unconnected-(U11-MISO-Pad13)") (class "Default")
      (node (ref "U11") (pin "13") (pinfunction "MISO_13") (pintype "bidirectional"))
    )
    (net (code "136") (name "unconnected-(U11-MODE-Pad3)") (class "Default")
      (node (ref "U11") (pin "3") (pinfunction "MODE_3") (pintype "bidirectional"))
    )
    (net (code "137") (name "unconnected-(U11-MOSI-Pad12)") (class "Default")
      (node (ref "U11") (pin "12") (pinfunction "MOSI_12") (pintype "bidirectional"))
    )
    (net (code "138") (name "unconnected-(U11-NC-Pad16)") (class "Default")
      (node (ref "U11") (pin "16") (pinfunction "NC_16") (pintype "bidirectional"))
    )
    (net (code "139") (name "unconnected-(U11-RX-Pad14)") (class "Default")
      (node (ref "U11") (pin "14") (pinfunction "RX_14") (pintype "bidirectional"))
    )
    (net (code "140") (name "unconnected-(U11-SCK-Pad11)") (class "Default")
      (node (ref "U11") (pin "11") (pinfunction "SCK_11") (pintype "bidirectional"))
    )
    (net (code "141") (name "unconnected-(U11-SCL-Pad18)") (class "Default")
      (node (ref "U11") (pin "18") (pinfunction "SCL_18") (pintype "bidirectional"))
    )
    (net (code "142") (name "unconnected-(U11-SDA-Pad17)") (class "Default")
      (node (ref "U11") (pin "17") (pinfunction "SDA_17") (pintype "bidirectional"))
    )
    (net (code "143") (name "unconnected-(U11-TX-Pad15)") (class "Default")
      (node (ref "U11") (pin "15") (pinfunction "TX_15") (pintype "bidirectional"))
    )
    (net (code "144") (name "unconnected-(U11-VUSB-Pad26)") (class "Default")
      (node (ref "U11") (pin "26") (pinfunction "VUSB_26") (pintype "bidirectional"))
    )
  )
)
